# ESP32.net
KiCad netlist of a schematic drawn in Altium Designer
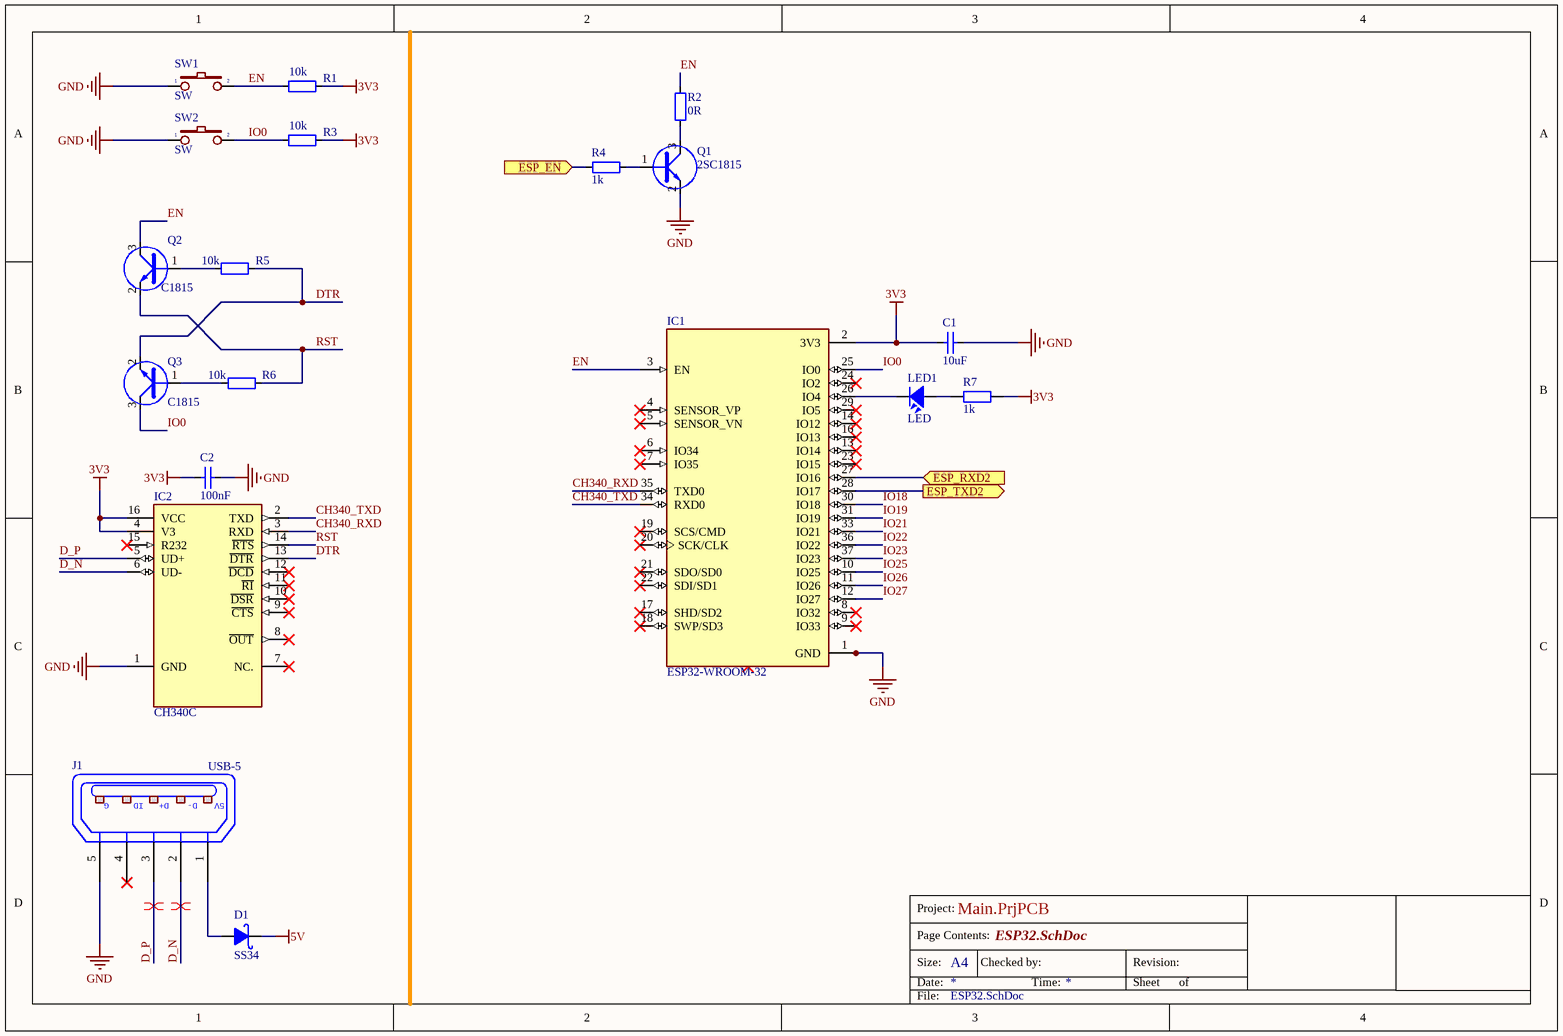
[diagram p0: ESP32.SchDoc]

(export (version "E")
  (design (tool "Eeschema 10.0.6"))
  (components
    (comp (ref "C1")
      (value "10uF")
      (footprint "CAP_0805")
      (description "Capacitor")
      (fields (field (name "PUBLISHER") "Altium Limited"))
      (libsource (lib "My Library") (part "CapSMD"))
    )
    (comp (ref "C2")
      (value "100nF")
      (footprint "CAP_0805")
      (description "Capacitor")
      (fields (field (name "PUBLISHER") "Altium Limited"))
      (libsource (lib "My Library") (part "CapSMD"))
    )
    (comp (ref "D1")
      (value "SS34")
      (footprint "DO-214AC(SMA)")
      (description "Diode Schottky SS34")
      (libsource (lib "My Library") (part "Diode Schottky"))
    )
    (comp (ref "IC1")
      (value "ESP32-WROOM-32")
      (footprint "MODULE_ESP32-WROOM-32")
      (description "Bluetooth, WiFi Transceiver Module 2.4GHz ~ 2.5GHz Surface Mount")
      (fields (field (name "MF") "Espressif Systems") (field (name "DIGI-KEY_PART_NUMBER") "1904-1010-1-ND"))
      (libsource (lib "My Library") (part "ESP32-WROOM-32"))
    )
    (comp (ref "IC2") (value "CH340C") (footprint "SO16") (libsource (lib "My Library") (part "CH340C")))
    (comp (ref "J1")
      (value "USB-5")
      (footprint "USB-M4")
      (fields
        (field (name "MANUFACTURER") "FCI")
        (field (name "MANUFACTURER PART NUMBER") "10118193-0001LF")
        (field (name ".CREATOR") "MM")
        (field (name ".CHECKED PCB") "RF")
        (field (name ".CHECKED SCH") "MM")
      )
      (libsource (lib "My Library") (part "USB-5"))
    )
    (comp (ref "LED1")
      (value "LED")
      (footprint "LED-0805-Blue")
      (description "LED Single colour Green and Red")
      (libsource (lib "My Library") (part "LED"))
    )
    (comp (ref "Q1")
      (value "2SC1815")
      (footprint "SOT23D")
      (description "NPN 600mW, ECB")
      (libsource (lib "My Library") (part "C1815"))
    )
    (comp (ref "Q2")
      (value "C1815")
      (footprint "SOT23D")
      (description "NPN 600mW, ECB")
      (libsource (lib "My Library") (part "2SC1815"))
    )
    (comp (ref "Q3")
      (value "C1815")
      (footprint "SOT23D")
      (description "NPN 600mW, ECB")
      (libsource (lib "") (part "2SC1815_1"))
    )
    (comp (ref "R1")
      (value "10k")
      (footprint "RES-SMD-0805")
      (description "Resistor")
      (fields
        (field (name "MANUFACTURER") "Generic Components")
        (field (name "PUBLISHER") "Altium Hobart Technology Centre")
      )
      (libsource (lib "My Library") (part "Resistor - SMD"))
    )
    (comp (ref "R2")
      (value "0R")
      (footprint "RES-SMD-0805")
      (description "Resistor")
      (fields
        (field (name "MANUFACTURER") "Generic Components")
        (field (name "PUBLISHER") "Altium Hobart Technology Centre")
      )
      (libsource (lib "My Library") (part "Resistor - SMD"))
    )
    (comp (ref "R3")
      (value "10k")
      (footprint "RES-SMD-0805")
      (description "Resistor")
      (fields
        (field (name "MANUFACTURER") "Generic Components")
        (field (name "PUBLISHER") "Altium Hobart Technology Centre")
      )
      (libsource (lib "My Library") (part "Resistor - SMD"))
    )
    (comp (ref "R4")
      (value "1k")
      (footprint "RES-SMD-0805")
      (description "Resistor")
      (fields
        (field (name "MANUFACTURER") "Generic Components")
        (field (name "PUBLISHER") "Altium Hobart Technology Centre")
      )
      (libsource (lib "My Library") (part "Resistor - SMD"))
    )
    (comp (ref "R5")
      (value "10k")
      (footprint "RES-SMD-0805")
      (description "Resistor")
      (fields
        (field (name "MANUFACTURER") "Generic Components")
        (field (name "PUBLISHER") "Altium Hobart Technology Centre")
      )
      (libsource (lib "My Library") (part "Resistor - SMD"))
    )
    (comp (ref "R6")
      (value "10k")
      (footprint "RES-SMD-0805")
      (description "Resistor")
      (fields
        (field (name "MANUFACTURER") "Generic Components")
        (field (name "PUBLISHER") "Altium Hobart Technology Centre")
      )
      (libsource (lib "My Library") (part "Resistor - SMD"))
    )
    (comp (ref "R7")
      (value "1k")
      (footprint "RES-SMD-0805")
      (description "Resistor SMD")
      (fields
        (field (name "MANUFACTURER") "Generic Components")
        (field (name "PUBLISHER") "Altium Hobart Technology Centre")
      )
      (libsource (lib "") (part "Resistor - SMD_1"))
    )
    (comp (ref "SW1")
      (value "SW")
      (footprint "SW 3x2x4")
      (description "Switch button 2 pin")
      (libsource (lib "My Library") (part "SW2"))
    )
    (comp (ref "SW2")
      (value "SW")
      (footprint "SW 3x2x4")
      (description "Switch button 2 pin")
      (libsource (lib "My Library") (part "SW2"))
    )
  )
  (nets
    (net (code "1") (name "/CH340_RXD") (class "Default")
      (node (ref "IC1") (pin "35") (pinfunction "TXD0_35") (pintype "bidirectional"))
      (node (ref "IC2") (pin "3") (pinfunction "RXD_3") (pintype "input"))
    )
    (net (code "2") (name "/CH340_TXD") (class "Default")
      (node (ref "IC1") (pin "34") (pinfunction "RXD0_34") (pintype "bidirectional"))
      (node (ref "IC2") (pin "2") (pinfunction "TXD_2") (pintype "output"))
    )
    (net (code "3") (name "/DTR") (class "Default")
      (node (ref "IC2") (pin "13") (pinfunction "~{DTR}_13") (pintype "output"))
      (node (ref "Q3") (pin "2") (pinfunction "E_2") (pintype "passive"))
      (node (ref "R5") (pin "1") (pinfunction "1_1") (pintype "passive"))
    )
    (net (code "4") (name "/D_N") (class "Default")
      (node (ref "IC2") (pin "6") (pinfunction "UD-_6") (pintype "bidirectional"))
      (node (ref "J1") (pin "2") (pinfunction "P2_2") (pintype "passive"))
    )
    (net (code "5") (name "/D_P") (class "Default")
      (node (ref "IC2") (pin "5") (pinfunction "UD+_5") (pintype "bidirectional"))
      (node (ref "J1") (pin "3") (pinfunction "P3_3") (pintype "passive"))
    )
    (net (code "6") (name "/EN") (class "Default")
      (node (ref "IC1") (pin "3") (pinfunction "EN_3") (pintype "input"))
      (node (ref "Q2") (pin "3") (pinfunction "C_3") (pintype "passive"))
      (node (ref "R1") (pin "2") (pinfunction "2_2") (pintype "passive"))
      (node (ref "R2") (pin "2") (pinfunction "2_2") (pintype "passive"))
      (node (ref "SW1") (pin "2") (pinfunction "2_2") (pintype "passive"))
    )
    (net (code "7") (name "/ESP_EN") (class "Default")
      (node (ref "R4") (pin "2") (pinfunction "2_2") (pintype "passive"))
    )
    (net (code "8") (name "/ESP_RXD2") (class "Default")
      (node (ref "IC1") (pin "27") (pinfunction "IO16_27") (pintype "bidirectional"))
    )
    (net (code "9") (name "/ESP_TXD2") (class "Default")
      (node (ref "IC1") (pin "28") (pinfunction "IO17_28") (pintype "bidirectional"))
    )
    (net (code "10") (name "/IO0") (class "Default")
      (node (ref "IC1") (pin "25") (pinfunction "IO0_25") (pintype "bidirectional"))
      (node (ref "Q3") (pin "3") (pinfunction "C_3") (pintype "passive"))
      (node (ref "R3") (pin "2") (pinfunction "2_2") (pintype "passive"))
      (node (ref "SW2") (pin "2") (pinfunction "2_2") (pintype "passive"))
    )
    (net (code "11") (name "/IO18") (class "Default")
      (node (ref "IC1") (pin "30") (pinfunction "IO18_30") (pintype "bidirectional"))
    )
    (net (code "12") (name "/IO19") (class "Default")
      (node (ref "IC1") (pin "31") (pinfunction "IO19_31") (pintype "bidirectional"))
    )
    (net (code "13") (name "/IO21") (class "Default")
      (node (ref "IC1") (pin "33") (pinfunction "IO21_33") (pintype "bidirectional"))
    )
    (net (code "14") (name "/IO22") (class "Default")
      (node (ref "IC1") (pin "36") (pinfunction "IO22_36") (pintype "bidirectional"))
    )
    (net (code "15") (name "/IO23") (class "Default")
      (node (ref "IC1") (pin "37") (pinfunction "IO23_37") (pintype "bidirectional"))
    )
    (net (code "16") (name "/IO25") (class "Default")
      (node (ref "IC1") (pin "10") (pinfunction "IO25_10") (pintype "bidirectional"))
    )
    (net (code "17") (name "/IO26") (class "Default")
      (node (ref "IC1") (pin "11") (pinfunction "IO26_11") (pintype "bidirectional"))
    )
    (net (code "18") (name "/IO27") (class "Default")
      (node (ref "IC1") (pin "12") (pinfunction "IO27_12") (pintype "bidirectional"))
    )
    (net (code "19") (name "/RST") (class "Default")
      (node (ref "IC2") (pin "14") (pinfunction "~{RTS}_14") (pintype "output"))
      (node (ref "Q2") (pin "2") (pinfunction "E_2") (pintype "passive"))
      (node (ref "R6") (pin "1") (pinfunction "1_1") (pintype "passive"))
    )
    (net (code "20") (name "3V3") (class "Default")
      (node (ref "C1") (pin "1") (pinfunction "1_1") (pintype "passive"))
      (node (ref "C2") (pin "1") (pinfunction "1_1") (pintype "passive"))
      (node (ref "IC1") (pin "2") (pinfunction "3V3_2") (pintype "power_in"))
      (node (ref "IC2") (pin "16") (pinfunction "VCC_16") (pintype "power_in"))
      (node (ref "IC2") (pin "4") (pinfunction "V3_4") (pintype "power_in"))
      (node (ref "R1") (pin "1") (pinfunction "1_1") (pintype "passive"))
      (node (ref "R3") (pin "1") (pinfunction "1_1") (pintype "passive"))
      (node (ref "R7") (pin "1") (pinfunction "1_1") (pintype "passive"))
    )
    (net (code "21") (name "5V") (class "Default")
      (node (ref "D1") (pin "2") (pinfunction "K_2") (pintype "passive"))
    )
    (net (code "22") (name "GND") (class "Default")
      (node (ref "C1") (pin "2") (pinfunction "2_2") (pintype "passive"))
      (node (ref "C2") (pin "2") (pinfunction "2_2") (pintype "passive"))
      (node (ref "IC1") (pin "1") (pinfunction "GND_1") (pintype "power_in"))
      (node (ref "IC1") (pin "15") (pinfunction "GND_15") (pintype "power_in"))
      (node (ref "IC1") (pin "38") (pinfunction "GND_38") (pintype "power_in"))
      (node (ref "IC1") (pin "39_1") (pinfunction "GND_39_1") (pintype "power_in"))
      (node (ref "IC1") (pin "39_10") (pinfunction "GND_39_10") (pintype "power_in"))
      (node (ref "IC1") (pin "39_11") (pinfunction "GND_39_11") (pintype "power_in"))
      (node (ref "IC1") (pin "39_12") (pinfunction "GND_39_12") (pintype "power_in"))
      (node (ref "IC1") (pin "39_13") (pinfunction "GND_39_13") (pintype "power_in"))
      (node (ref "IC1") (pin "39_14") (pinfunction "GND_39_14") (pintype "power_in"))
      (node (ref "IC1") (pin "39_15") (pinfunction "GND_39_15") (pintype "power_in"))
      (node (ref "IC1") (pin "39_16") (pinfunction "GND_39_16") (pintype "power_in"))
      (node (ref "IC1") (pin "39_17") (pinfunction "GND_39_17") (pintype "power_in"))
      (node (ref "IC1") (pin "39_18") (pinfunction "GND_39_18") (pintype "power_in"))
      (node (ref "IC1") (pin "39_19") (pinfunction "GND_39_19") (pintype "power_in"))
      (node (ref "IC1") (pin "39_2") (pinfunction "GND_39_2") (pintype "power_in"))
      (node (ref "IC1") (pin "39_20") (pinfunction "GND_39_20") (pintype "power_in"))
      (node (ref "IC1") (pin "39_21") (pinfunction "GND_39_21") (pintype "power_in"))
      (node (ref "IC1") (pin "39_3") (pinfunction "GND_39_3") (pintype "power_in"))
      (node (ref "IC1") (pin "39_4") (pinfunction "GND_39_4") (pintype "power_in"))
      (node (ref "IC1") (pin "39_5") (pinfunction "GND_39_5") (pintype "power_in"))
      (node (ref "IC1") (pin "39_6") (pinfunction "GND_39_6") (pintype "power_in"))
      (node (ref "IC1") (pin "39_7") (pinfunction "GND_39_7") (pintype "power_in"))
      (node (ref "IC1") (pin "39_8") (pinfunction "GND_39_8") (pintype "power_in"))
      (node (ref "IC1") (pin "39_9") (pinfunction "GND_39_9") (pintype "power_in"))
      (node (ref "IC2") (pin "1") (pinfunction "GND_1") (pintype "power_in"))
      (node (ref "J1") (pin "5") (pinfunction "P5_5") (pintype "passive"))
      (node (ref "Q1") (pin "2") (pinfunction "E_2") (pintype "passive"))
      (node (ref "SW1") (pin "1") (pinfunction "1_1") (pintype "passive"))
      (node (ref "SW2") (pin "1") (pinfunction "1_1") (pintype "passive"))
    )
    (net (code "23") (name "Net-(D1-A)") (class "Default")
      (node (ref "D1") (pin "1") (pinfunction "A_1") (pintype "passive"))
      (node (ref "J1") (pin "1") (pinfunction "P1_1") (pintype "passive"))
    )
    (net (code "24") (name "Net-(IC1-IO4)") (class "Default")
      (node (ref "IC1") (pin "26") (pinfunction "IO4_26") (pintype "bidirectional"))
      (node (ref "LED1") (pin "2") (pinfunction "2_2") (pintype "passive"))
    )
    (net (code "25") (name "Net-(LED1-Pad1)") (class "Default")
      (node (ref "LED1") (pin "1") (pinfunction "1_1") (pintype "passive"))
      (node (ref "R7") (pin "2") (pinfunction "2_2") (pintype "passive"))
    )
    (net (code "26") (name "Net-(Q1-B)") (class "Default")
      (node (ref "Q1") (pin "1") (pinfunction "B_1") (pintype "passive"))
      (node (ref "R4") (pin "1") (pinfunction "1_1") (pintype "passive"))
    )
    (net (code "27") (name "Net-(Q1-C)") (class "Default")
      (node (ref "Q1") (pin "3") (pinfunction "C_3") (pintype "passive"))
      (node (ref "R2") (pin "1") (pinfunction "1_1") (pintype "passive"))
    )
    (net (code "28") (name "Net-(Q2-B)") (class "Default")
      (node (ref "Q2") (pin "1") (pinfunction "B_1") (pintype "passive"))
      (node (ref "R5") (pin "2") (pinfunction "2_2") (pintype "passive"))
    )
    (net (code "29") (name "Net-(Q3-B)") (class "Default")
      (node (ref "Q3") (pin "1") (pinfunction "B_1") (pintype "passive"))
      (node (ref "R6") (pin "2") (pinfunction "2_2") (pintype "passive"))
    )
    (net (code "30") (name "unconnected-(IC1-IO2-Pad24)") (class "Default")
      (node (ref "IC1") (pin "24") (pinfunction "IO2_24") (pintype "bidirectional+no_connect"))
    )
    (net (code "31") (name "unconnected-(IC1-IO5-Pad29)") (class "Default")
      (node (ref "IC1") (pin "29") (pinfunction "IO5_29") (pintype "bidirectional+no_connect"))
    )
    (net (code "32") (name "unconnected-(IC1-IO12-Pad14)") (class "Default")
      (node (ref "IC1") (pin "14") (pinfunction "IO12_14") (pintype "bidirectional+no_connect"))
    )
    (net (code "33") (name "unconnected-(IC1-IO13-Pad16)") (class "Default")
      (node (ref "IC1") (pin "16") (pinfunction "IO13_16") (pintype "bidirectional+no_connect"))
    )
    (net (code "34") (name "unconnected-(IC1-IO14-Pad13)") (class "Default")
      (node (ref "IC1") (pin "13") (pinfunction "IO14_13") (pintype "bidirectional+no_connect"))
    )
    (net (code "35") (name "unconnected-(IC1-IO15-Pad23)") (class "Default")
      (node (ref "IC1") (pin "23") (pinfunction "IO15_23") (pintype "bidirectional+no_connect"))
    )
    (net (code "36") (name "unconnected-(IC1-IO32-Pad8)") (class "Default")
      (node (ref "IC1") (pin "8") (pinfunction "IO32_8") (pintype "bidirectional+no_connect"))
    )
    (net (code "37") (name "unconnected-(IC1-IO33-Pad9)") (class "Default")
      (node (ref "IC1") (pin "9") (pinfunction "IO33_9") (pintype "bidirectional+no_connect"))
    )
    (net (code "38") (name "unconnected-(IC1-IO34-Pad6)") (class "Default")
      (node (ref "IC1") (pin "6") (pinfunction "IO34_6") (pintype "input+no_connect"))
    )
    (net (code "39") (name "unconnected-(IC1-IO35-Pad7)") (class "Default")
      (node (ref "IC1") (pin "7") (pinfunction "IO35_7") (pintype "input+no_connect"))
    )
    (net (code "40") (name "unconnected-(IC1-SCK{slash}CLK-Pad20)") (class "Default")
      (node (ref "IC1") (pin "20") (pinfunction "SCK/CLK_20") (pintype "bidirectional+no_connect"))
    )
    (net (code "41") (name "unconnected-(IC1-SCS{slash}CMD-Pad19)") (class "Default")
      (node (ref "IC1") (pin "19") (pinfunction "SCS/CMD_19") (pintype "bidirectional+no_connect"))
    )
    (net (code "42") (name "unconnected-(IC1-SDI{slash}SD1-Pad22)") (class "Default")
      (node (ref "IC1") (pin "22") (pinfunction "SDI/SD1_22") (pintype "bidirectional+no_connect"))
    )
    (net (code "43") (name "unconnected-(IC1-SDO{slash}SD0-Pad21)") (class "Default")
      (node (ref "IC1") (pin "21") (pinfunction "SDO/SD0_21") (pintype "bidirectional+no_connect"))
    )
    (net (code "44") (name "unconnected-(IC1-SENSOR_VN-Pad5)") (class "Default")
      (node (ref "IC1") (pin "5") (pinfunction "SENSOR_VN_5") (pintype "input+no_connect"))
    )
    (net (code "45") (name "unconnected-(IC1-SENSOR_VP-Pad4)") (class "Default")
      (node (ref "IC1") (pin "4") (pinfunction "SENSOR_VP_4") (pintype "input+no_connect"))
    )
    (net (code "46") (name "unconnected-(IC1-SHD{slash}SD2-Pad17)") (class "Default")
      (node (ref "IC1") (pin "17") (pinfunction "SHD/SD2_17") (pintype "bidirectional+no_connect"))
    )
    (net (code "47") (name "unconnected-(IC1-SWP{slash}SD3-Pad18)") (class "Default")
      (node (ref "IC1") (pin "18") (pinfunction "SWP/SD3_18") (pintype "bidirectional+no_connect"))
    )
    (net (code "48") (name "unconnected-(IC2-NC.-Pad7)") (class "Default")
      (node (ref "IC2") (pin "7") (pinfunction "NC._7") (pintype "passive+no_connect"))
    )
    (net (code "49") (name "unconnected-(IC2-R232-Pad15)") (class "Default")
      (node (ref "IC2") (pin "15") (pinfunction "R232_15") (pintype "input+no_connect"))
    )
    (net (code "50") (name "unconnected-(IC2-~{CTS}-Pad9)") (class "Default")
      (node (ref "IC2") (pin "9") (pinfunction "~{CTS}_9") (pintype "input+no_connect"))
    )
    (net (code "51") (name "unconnected-(IC2-~{DCD}-Pad12)") (class "Default")
      (node (ref "IC2") (pin "12") (pinfunction "~{DCD}_12") (pintype "input+no_connect"))
    )
    (net (code "52") (name "unconnected-(IC2-~{DSR}-Pad10)") (class "Default")
      (node (ref "IC2") (pin "10") (pinfunction "~{DSR}_10") (pintype "input+no_connect"))
    )
    (net (code "53") (name "unconnected-(IC2-~{OUT}-Pad8)") (class "Default")
      (node (ref "IC2") (pin "8") (pinfunction "~{OUT}_8") (pintype "output+no_connect"))
    )
    (net (code "54") (name "unconnected-(IC2-~{RI}-Pad11)") (class "Default")
      (node (ref "IC2") (pin "11") (pinfunction "~{RI}_11") (pintype "input+no_connect"))
    )
    (net (code "55") (name "unconnected-(J1-P4-Pad4)") (class "Default")
      (node (ref "J1") (pin "4") (pinfunction "P4_4") (pintype "passive+no_connect"))
    )
  )
)
